# Arduino_DUE_V02b_Template.net
KiCad netlist of a schematic drawn in Altium Designer
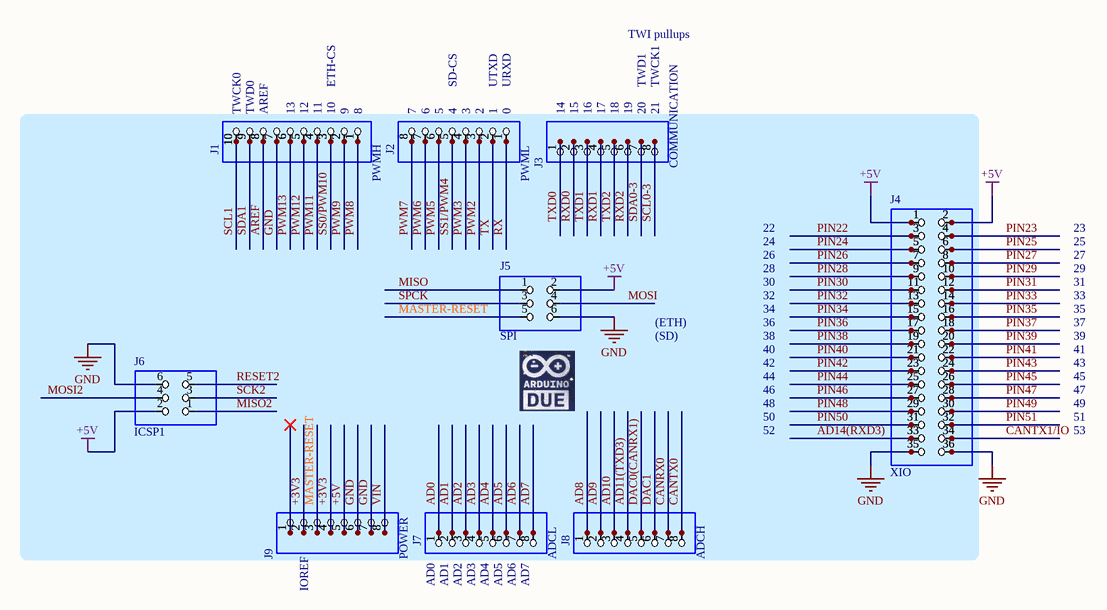
[diagram p0: Arduino_DUE_V02b_Template.SchDoc]

(export (version "E")
  (design (tool "Eeschema 10.0.6"))
  (components
    (comp (ref "J1") (value "PWMH") (footprint "1X10") (libsource (lib "SmartPrj") (part "PINHD-1X10")))
    (comp (ref "J2") (value "PWML") (footprint "1X08") (libsource (lib "SmartPrj") (part "PINHD-1X8")))
    (comp (ref "J3")
      (value "COMMUNICATION")
      (footprint "1X08")
      (libsource (lib "SmartPrj") (part "PINHD-1X8"))
    )
    (comp (ref "J4") (value "XIO") (footprint "2X18") (libsource (lib "SmartPrj") (part "PINHD-2X18")))
    (comp (ref "J5") (value "SPI") (footprint "2X03") (libsource (lib "SmartPrj") (part "PINHD-2X3")))
    (comp (ref "J6") (value "ICSP1") (footprint "2X03") (libsource (lib "SmartPrj") (part "PINHD-2X3")))
    (comp (ref "J7") (value "ADCL") (footprint "1X08") (libsource (lib "SmartPrj") (part "PINHD-1X8")))
    (comp (ref "J8") (value "ADCH") (footprint "1X08") (libsource (lib "SmartPrj") (part "PINHD-1X8")))
    (comp (ref "J9") (value "POWER") (footprint "1X08") (libsource (lib "SmartPrj") (part "PINHD-1X8")))
  )
  (nets
    (net (code "1") (name "+5V") (class "Default")
      (node (ref "J4") (pin "1") (pinfunction "1_1") (pintype "passive"))
      (node (ref "J4") (pin "2") (pinfunction "2_2") (pintype "passive"))
      (node (ref "J5") (pin "2") (pinfunction "2_2") (pintype "passive"))
      (node (ref "J6") (pin "2") (pinfunction "2_2") (pintype "passive"))
      (node (ref "J9") (pin "5") (pinfunction "5_5") (pintype "passive"))
    )
    (net (code "2") (name "/+3V3") (class "Default")
      (node (ref "J9") (pin "2") (pinfunction "2_2") (pintype "passive"))
      (node (ref "J9") (pin "4") (pinfunction "4_4") (pintype "passive"))
    )
    (net (code "3") (name "/AD0") (class "Default")
      (node (ref "J7") (pin "1") (pinfunction "1_1") (pintype "passive"))
    )
    (net (code "4") (name "/AD1") (class "Default")
      (node (ref "J7") (pin "2") (pinfunction "2_2") (pintype "passive"))
    )
    (net (code "5") (name "/AD2") (class "Default")
      (node (ref "J7") (pin "3") (pinfunction "3_3") (pintype "passive"))
    )
    (net (code "6") (name "/AD3") (class "Default")
      (node (ref "J7") (pin "4") (pinfunction "4_4") (pintype "passive"))
    )
    (net (code "7") (name "/AD4") (class "Default")
      (node (ref "J7") (pin "5") (pinfunction "5_5") (pintype "passive"))
    )
    (net (code "8") (name "/AD5") (class "Default")
      (node (ref "J7") (pin "6") (pinfunction "6_6") (pintype "passive"))
    )
    (net (code "9") (name "/AD6") (class "Default")
      (node (ref "J7") (pin "7") (pinfunction "7_7") (pintype "passive"))
    )
    (net (code "10") (name "/AD7") (class "Default")
      (node (ref "J7") (pin "8") (pinfunction "8_8") (pintype "passive"))
    )
    (net (code "11") (name "/AD8") (class "Default")
      (node (ref "J8") (pin "1") (pinfunction "1_1") (pintype "passive"))
    )
    (net (code "12") (name "/AD9") (class "Default")
      (node (ref "J8") (pin "2") (pinfunction "2_2") (pintype "passive"))
    )
    (net (code "13") (name "/AD10") (class "Default")
      (node (ref "J8") (pin "3") (pinfunction "3_3") (pintype "passive"))
    )
    (net (code "14") (name "/AD11(TXD3)") (class "Default")
      (node (ref "J8") (pin "4") (pinfunction "4_4") (pintype "passive"))
    )
    (net (code "15") (name "/AD14(RXD3)") (class "Default")
      (node (ref "J4") (pin "33") (pinfunction "33_33") (pintype "passive"))
    )
    (net (code "16") (name "/AREF") (class "Default")
      (node (ref "J1") (pin "8") (pinfunction "8_8") (pintype "passive"))
    )
    (net (code "17") (name "/CANRX0") (class "Default")
      (node (ref "J8") (pin "7") (pinfunction "7_7") (pintype "passive"))
    )
    (net (code "18") (name "/CANTX0") (class "Default")
      (node (ref "J8") (pin "8") (pinfunction "8_8") (pintype "passive"))
    )
    (net (code "19") (name "/CANTX1{slash}IO") (class "Default")
      (node (ref "J4") (pin "34") (pinfunction "34_34") (pintype "passive"))
    )
    (net (code "20") (name "/DAC0(CANRX1)") (class "Default")
      (node (ref "J8") (pin "5") (pinfunction "5_5") (pintype "passive"))
    )
    (net (code "21") (name "/DAC1") (class "Default")
      (node (ref "J8") (pin "6") (pinfunction "6_6") (pintype "passive"))
    )
    (net (code "22") (name "/MASTER-RESET") (class "Default")
      (node (ref "J5") (pin "5") (pinfunction "5_5") (pintype "passive"))
      (node (ref "J9") (pin "3") (pinfunction "3_3") (pintype "passive"))
    )
    (net (code "23") (name "/MISO") (class "Default")
      (node (ref "J5") (pin "1") (pinfunction "1_1") (pintype "passive"))
    )
    (net (code "24") (name "/MISO2") (class "Default")
      (node (ref "J6") (pin "1") (pinfunction "1_1") (pintype "passive"))
    )
    (net (code "25") (name "/MOSI") (class "Default")
      (node (ref "J5") (pin "4") (pinfunction "4_4") (pintype "passive"))
    )
    (net (code "26") (name "/MOSI2") (class "Default")
      (node (ref "J6") (pin "4") (pinfunction "4_4") (pintype "passive"))
    )
    (net (code "27") (name "/PIN22") (class "Default")
      (node (ref "J4") (pin "3") (pinfunction "3_3") (pintype "passive"))
    )
    (net (code "28") (name "/PIN23") (class "Default")
      (node (ref "J4") (pin "4") (pinfunction "4_4") (pintype "passive"))
    )
    (net (code "29") (name "/PIN24") (class "Default")
      (node (ref "J4") (pin "5") (pinfunction "5_5") (pintype "passive"))
    )
    (net (code "30") (name "/PIN25") (class "Default")
      (node (ref "J4") (pin "6") (pinfunction "6_6") (pintype "passive"))
    )
    (net (code "31") (name "/PIN26") (class "Default")
      (node (ref "J4") (pin "7") (pinfunction "7_7") (pintype "passive"))
    )
    (net (code "32") (name "/PIN27") (class "Default")
      (node (ref "J4") (pin "8") (pinfunction "8_8") (pintype "passive"))
    )
    (net (code "33") (name "/PIN28") (class "Default")
      (node (ref "J4") (pin "9") (pinfunction "9_9") (pintype "passive"))
    )
    (net (code "34") (name "/PIN29") (class "Default")
      (node (ref "J4") (pin "10") (pinfunction "10_10") (pintype "passive"))
    )
    (net (code "35") (name "/PIN30") (class "Default")
      (node (ref "J4") (pin "11") (pinfunction "11_11") (pintype "passive"))
    )
    (net (code "36") (name "/PIN31") (class "Default")
      (node (ref "J4") (pin "12") (pinfunction "12_12") (pintype "passive"))
    )
    (net (code "37") (name "/PIN32") (class "Default")
      (node (ref "J4") (pin "13") (pinfunction "13_13") (pintype "passive"))
    )
    (net (code "38") (name "/PIN33") (class "Default")
      (node (ref "J4") (pin "14") (pinfunction "14_14") (pintype "passive"))
    )
    (net (code "39") (name "/PIN34") (class "Default")
      (node (ref "J4") (pin "15") (pinfunction "15_15") (pintype "passive"))
    )
    (net (code "40") (name "/PIN35") (class "Default")
      (node (ref "J4") (pin "16") (pinfunction "16_16") (pintype "passive"))
    )
    (net (code "41") (name "/PIN36") (class "Default")
      (node (ref "J4") (pin "17") (pinfunction "17_17") (pintype "passive"))
    )
    (net (code "42") (name "/PIN37") (class "Default")
      (node (ref "J4") (pin "18") (pinfunction "18_18") (pintype "passive"))
    )
    (net (code "43") (name "/PIN38") (class "Default")
      (node (ref "J4") (pin "19") (pinfunction "19_19") (pintype "passive"))
    )
    (net (code "44") (name "/PIN39") (class "Default")
      (node (ref "J4") (pin "20") (pinfunction "20_20") (pintype "passive"))
    )
    (net (code "45") (name "/PIN40") (class "Default")
      (node (ref "J4") (pin "21") (pinfunction "21_21") (pintype "passive"))
    )
    (net (code "46") (name "/PIN41") (class "Default")
      (node (ref "J4") (pin "22") (pinfunction "22_22") (pintype "passive"))
    )
    (net (code "47") (name "/PIN42") (class "Default")
      (node (ref "J4") (pin "23") (pinfunction "23_23") (pintype "passive"))
    )
    (net (code "48") (name "/PIN43") (class "Default")
      (node (ref "J4") (pin "24") (pinfunction "24_24") (pintype "passive"))
    )
    (net (code "49") (name "/PIN44") (class "Default")
      (node (ref "J4") (pin "25") (pinfunction "25_25") (pintype "passive"))
    )
    (net (code "50") (name "/PIN45") (class "Default")
      (node (ref "J4") (pin "26") (pinfunction "26_26") (pintype "passive"))
    )
    (net (code "51") (name "/PIN46") (class "Default")
      (node (ref "J4") (pin "27") (pinfunction "27_27") (pintype "passive"))
    )
    (net (code "52") (name "/PIN47") (class "Default")
      (node (ref "J4") (pin "28") (pinfunction "28_28") (pintype "passive"))
    )
    (net (code "53") (name "/PIN48") (class "Default")
      (node (ref "J4") (pin "29") (pinfunction "29_29") (pintype "passive"))
    )
    (net (code "54") (name "/PIN49") (class "Default")
      (node (ref "J4") (pin "30") (pinfunction "30_30") (pintype "passive"))
    )
    (net (code "55") (name "/PIN50") (class "Default")
      (node (ref "J4") (pin "31") (pinfunction "31_31") (pintype "passive"))
    )
    (net (code "56") (name "/PIN51") (class "Default")
      (node (ref "J4") (pin "32") (pinfunction "32_32") (pintype "passive"))
    )
    (net (code "57") (name "/PWM2") (class "Default")
      (node (ref "J2") (pin "3") (pinfunction "3_3") (pintype "passive"))
    )
    (net (code "58") (name "/PWM3") (class "Default")
      (node (ref "J2") (pin "4") (pinfunction "4_4") (pintype "passive"))
    )
    (net (code "59") (name "/PWM5") (class "Default")
      (node (ref "J2") (pin "6") (pinfunction "6_6") (pintype "passive"))
    )
    (net (code "60") (name "/PWM6") (class "Default")
      (node (ref "J2") (pin "7") (pinfunction "7_7") (pintype "passive"))
    )
    (net (code "61") (name "/PWM7") (class "Default")
      (node (ref "J2") (pin "8") (pinfunction "8_8") (pintype "passive"))
    )
    (net (code "62") (name "/PWM8") (class "Default")
      (node (ref "J1") (pin "1") (pinfunction "1_1") (pintype "passive"))
    )
    (net (code "63") (name "/PWM9") (class "Default")
      (node (ref "J1") (pin "2") (pinfunction "2_2") (pintype "passive"))
    )
    (net (code "64") (name "/PWM11") (class "Default")
      (node (ref "J1") (pin "4") (pinfunction "4_4") (pintype "passive"))
    )
    (net (code "65") (name "/PWM12") (class "Default")
      (node (ref "J1") (pin "5") (pinfunction "5_5") (pintype "passive"))
    )
    (net (code "66") (name "/PWM13") (class "Default")
      (node (ref "J1") (pin "6") (pinfunction "6_6") (pintype "passive"))
    )
    (net (code "67") (name "/RESET2") (class "Default")
      (node (ref "J6") (pin "5") (pinfunction "5_5") (pintype "passive"))
    )
    (net (code "68") (name "/RX") (class "Default")
      (node (ref "J2") (pin "1") (pinfunction "1_1") (pintype "passive"))
    )
    (net (code "69") (name "/RXD0") (class "Default")
      (node (ref "J3") (pin "2") (pinfunction "2_2") (pintype "passive"))
    )
    (net (code "70") (name "/RXD1") (class "Default")
      (node (ref "J3") (pin "4") (pinfunction "4_4") (pintype "passive"))
    )
    (net (code "71") (name "/RXD2") (class "Default")
      (node (ref "J3") (pin "6") (pinfunction "6_6") (pintype "passive"))
    )
    (net (code "72") (name "/SCK2") (class "Default")
      (node (ref "J6") (pin "3") (pinfunction "3_3") (pintype "passive"))
    )
    (net (code "73") (name "/SCL0-3") (class "Default")
      (node (ref "J3") (pin "8") (pinfunction "8_8") (pintype "passive"))
    )
    (net (code "74") (name "/SCL1") (class "Default")
      (node (ref "J1") (pin "10") (pinfunction "10_10") (pintype "passive"))
    )
    (net (code "75") (name "/SDA0-3") (class "Default")
      (node (ref "J3") (pin "7") (pinfunction "7_7") (pintype "passive"))
    )
    (net (code "76") (name "/SDA1") (class "Default")
      (node (ref "J1") (pin "9") (pinfunction "9_9") (pintype "passive"))
    )
    (net (code "77") (name "/SPCK") (class "Default")
      (node (ref "J5") (pin "3") (pinfunction "3_3") (pintype "passive"))
    )
    (net (code "78") (name "/SS0{slash}PWM10") (class "Default")
      (node (ref "J1") (pin "3") (pinfunction "3_3") (pintype "passive"))
    )
    (net (code "79") (name "/SS1{slash}PWM4") (class "Default")
      (node (ref "J2") (pin "5") (pinfunction "5_5") (pintype "passive"))
    )
    (net (code "80") (name "/TX") (class "Default")
      (node (ref "J2") (pin "2") (pinfunction "2_2") (pintype "passive"))
    )
    (net (code "81") (name "/TXD0") (class "Default")
      (node (ref "J3") (pin "1") (pinfunction "1_1") (pintype "passive"))
    )
    (net (code "82") (name "/TXD1") (class "Default")
      (node (ref "J3") (pin "3") (pinfunction "3_3") (pintype "passive"))
    )
    (net (code "83") (name "/TXD2") (class "Default")
      (node (ref "J3") (pin "5") (pinfunction "5_5") (pintype "passive"))
    )
    (net (code "84") (name "/VIN") (class "Default")
      (node (ref "J9") (pin "8") (pinfunction "8_8") (pintype "passive"))
    )
    (net (code "85") (name "GND") (class "Default")
      (node (ref "J1") (pin "7") (pinfunction "7_7") (pintype "passive"))
      (node (ref "J4") (pin "35") (pinfunction "35_35") (pintype "passive"))
      (node (ref "J4") (pin "36") (pinfunction "36_36") (pintype "passive"))
      (node (ref "J5") (pin "6") (pinfunction "6_6") (pintype "passive"))
      (node (ref "J6") (pin "6") (pinfunction "6_6") (pintype "passive"))
      (node (ref "J9") (pin "6") (pinfunction "6_6") (pintype "passive"))
      (node (ref "J9") (pin "7") (pinfunction "7_7") (pintype "passive"))
    )
    (net (code "86") (name "unconnected-(J9-Pad1)") (class "Default")
      (node (ref "J9") (pin "1") (pinfunction "1_1") (pintype "passive+no_connect"))
    )
  )
)
